# RH030_2.net
KiCad netlist of a schematic drawn in EAGLE
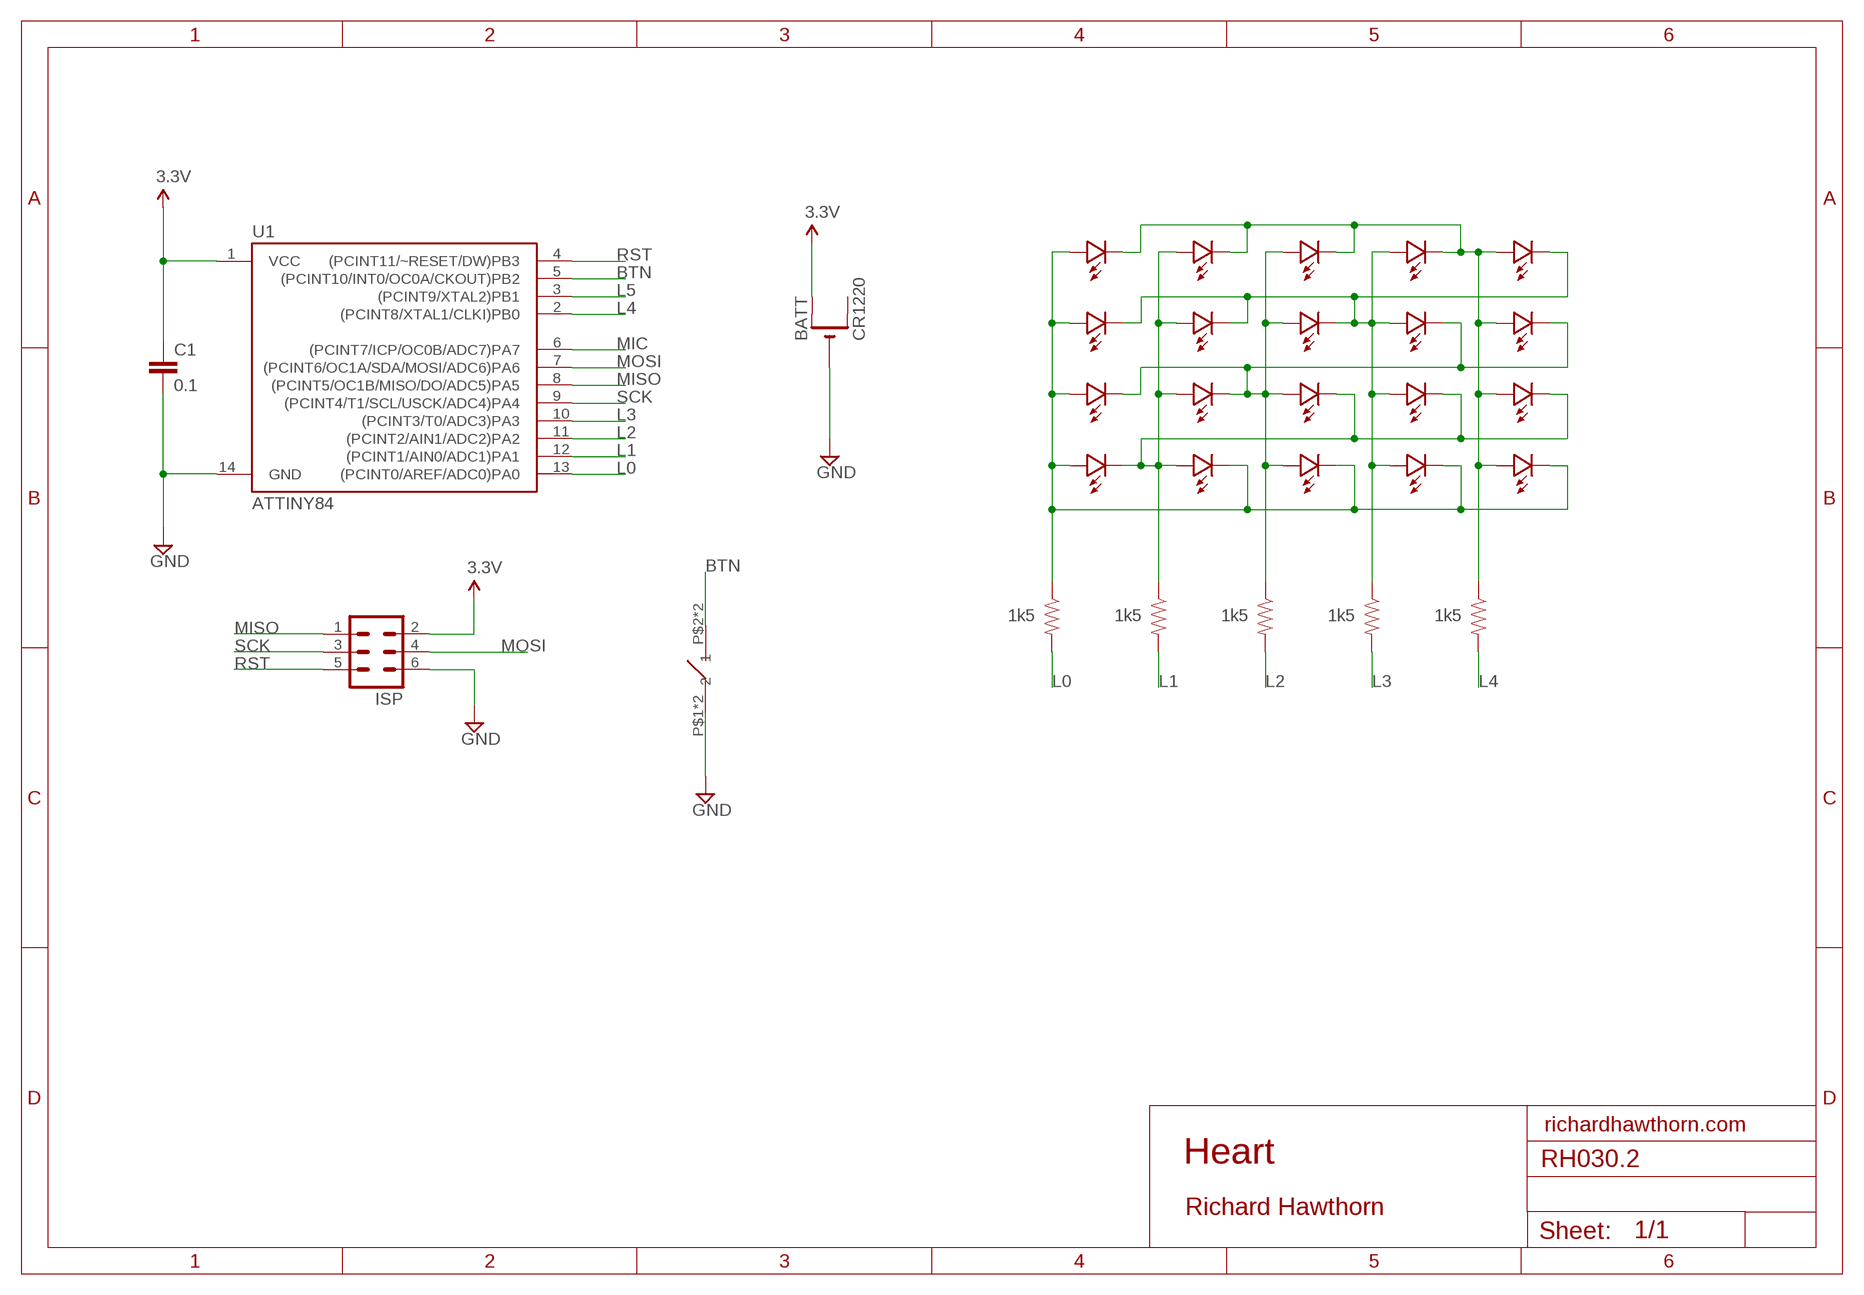
[diagram p0: schematic, sheet 1]

(export (version "E")
  (design (tool "Eeschema 10.0.6"))
  (components
    (comp (ref "BATT")
      (value "CR1220")
      (footprint "eagle-import:CR1220-SMD")
      (libsource (lib "eagle-import") (part "CR1220SMT"))
    )
    (comp (ref "BTN1")
      (value "TURTLE-3PIN")
      (footprint "eagle-import:TURTLE-3PIN")
      (libsource (lib "eagle-import") (part "TURTLE-3PIN"))
    )
    (comp (ref "C1")
      (value "0.1")
      (footprint "eagle-import:0603-CAP")
      (libsource (lib "eagle-import") (part "CAP0603-CAP"))
    )
    (comp (ref "ISP")
      (value "MA03-2")
      (footprint "eagle-import:MA03-2")
      (libsource (lib "eagle-import") (part "MA03-2"))
    )
    (comp (ref "LED1")
      (value "LED0603")
      (footprint "eagle-import:0603-LED")
      (libsource (lib "eagle-import") (part "LED0603"))
    )
    (comp (ref "LED2")
      (value "LED0603")
      (footprint "eagle-import:0603-LED")
      (libsource (lib "eagle-import") (part "LED0603"))
    )
    (comp (ref "LED3")
      (value "LED0603")
      (footprint "eagle-import:0603-LED")
      (libsource (lib "eagle-import") (part "LED0603"))
    )
    (comp (ref "LED4")
      (value "LED0603")
      (footprint "eagle-import:0603-LED")
      (libsource (lib "eagle-import") (part "LED0603"))
    )
    (comp (ref "LED5")
      (value "LED0603")
      (footprint "eagle-import:0603-LED")
      (libsource (lib "eagle-import") (part "LED0603"))
    )
    (comp (ref "LED6")
      (value "LED0603")
      (footprint "eagle-import:0603-LED")
      (libsource (lib "eagle-import") (part "LED0603"))
    )
    (comp (ref "LED7")
      (value "LED0603")
      (footprint "eagle-import:0603-LED")
      (libsource (lib "eagle-import") (part "LED0603"))
    )
    (comp (ref "LED8")
      (value "LED0603")
      (footprint "eagle-import:0603-LED")
      (libsource (lib "eagle-import") (part "LED0603"))
    )
    (comp (ref "LED9")
      (value "LED0603")
      (footprint "eagle-import:0603-LED")
      (libsource (lib "eagle-import") (part "LED0603"))
    )
    (comp (ref "LED10")
      (value "LED0603")
      (footprint "eagle-import:0603-LED")
      (libsource (lib "eagle-import") (part "LED0603"))
    )
    (comp (ref "LED11")
      (value "LED0603")
      (footprint "eagle-import:0603-LED")
      (libsource (lib "eagle-import") (part "LED0603"))
    )
    (comp (ref "LED12")
      (value "LED0603")
      (footprint "eagle-import:0603-LED")
      (libsource (lib "eagle-import") (part "LED0603"))
    )
    (comp (ref "LED13")
      (value "LED0603")
      (footprint "eagle-import:0603-LED")
      (libsource (lib "eagle-import") (part "LED0603"))
    )
    (comp (ref "LED14")
      (value "LED0603")
      (footprint "eagle-import:0603-LED")
      (libsource (lib "eagle-import") (part "LED0603"))
    )
    (comp (ref "LED15")
      (value "LED0603")
      (footprint "eagle-import:0603-LED")
      (libsource (lib "eagle-import") (part "LED0603"))
    )
    (comp (ref "LED16")
      (value "LED0603")
      (footprint "eagle-import:0603-LED")
      (libsource (lib "eagle-import") (part "LED0603"))
    )
    (comp (ref "LED17")
      (value "LED0603")
      (footprint "eagle-import:0603-LED")
      (libsource (lib "eagle-import") (part "LED0603"))
    )
    (comp (ref "LED18")
      (value "LED0603")
      (footprint "eagle-import:0603-LED")
      (libsource (lib "eagle-import") (part "LED0603"))
    )
    (comp (ref "LED19")
      (value "LED0603")
      (footprint "eagle-import:0603-LED")
      (libsource (lib "eagle-import") (part "LED0603"))
    )
    (comp (ref "LED20")
      (value "LED0603")
      (footprint "eagle-import:0603-LED")
      (libsource (lib "eagle-import") (part "LED0603"))
    )
    (comp (ref "R1")
      (value "1k5")
      (footprint "eagle-import:0603-RES")
      (libsource (lib "eagle-import") (part "RESISTOR0603-RES"))
    )
    (comp (ref "R2")
      (value "1k5")
      (footprint "eagle-import:0603-RES")
      (libsource (lib "eagle-import") (part "RESISTOR0603-RES"))
    )
    (comp (ref "R3")
      (value "1k5")
      (footprint "eagle-import:0603-RES")
      (libsource (lib "eagle-import") (part "RESISTOR0603-RES"))
    )
    (comp (ref "R4")
      (value "1k5")
      (footprint "eagle-import:0603-RES")
      (libsource (lib "eagle-import") (part "RESISTOR0603-RES"))
    )
    (comp (ref "R5")
      (value "1k5")
      (footprint "eagle-import:0603-RES")
      (libsource (lib "eagle-import") (part "RESISTOR0603-RES"))
    )
    (comp (ref "U1")
      (value "ATTINY84")
      (footprint "eagle-import:SO14")
      (libsource (lib "eagle-import") (part "ATTINY84"))
    )
  )
  (nets
    (net (code "1") (name "/BTN") (class "Default")
      (node (ref "BTN1") (pin "P$2") (pinfunction "2_P$2") (pintype "bidirectional"))
      (node (ref "BTN1") (pin "P$4") (pinfunction "2_P$4") (pintype "bidirectional"))
      (node (ref "U1") (pin "5") (pinfunction "(PCINT10/INT0/OC0A/CKOUT)PB2_5") (pintype "bidirectional"))
    )
    (net (code "2") (name "/L0") (class "Default")
      (node (ref "R1") (pin "2") (pinfunction "2_2") (pintype "passive"))
      (node (ref "U1") (pin "13") (pinfunction "(PCINT0/AREF/ADC0)PA0_13") (pintype "bidirectional"))
    )
    (net (code "3") (name "/L1") (class "Default")
      (node (ref "R2") (pin "2") (pinfunction "2_2") (pintype "passive"))
      (node (ref "U1") (pin "12") (pinfunction "(PCINT1/AIN0/ADC1)PA1_12") (pintype "bidirectional"))
    )
    (net (code "4") (name "/L2") (class "Default")
      (node (ref "R3") (pin "2") (pinfunction "2_2") (pintype "passive"))
      (node (ref "U1") (pin "11") (pinfunction "(PCINT2/AIN1/ADC2)PA2_11") (pintype "bidirectional"))
    )
    (net (code "5") (name "/L3") (class "Default")
      (node (ref "R4") (pin "2") (pinfunction "2_2") (pintype "passive"))
      (node (ref "U1") (pin "10") (pinfunction "(PCINT3/T0/ADC3)PA3_10") (pintype "bidirectional"))
    )
    (net (code "6") (name "/L4") (class "Default")
      (node (ref "R5") (pin "2") (pinfunction "2_2") (pintype "passive"))
      (node (ref "U1") (pin "2") (pinfunction "(PCINT8/XTAL1/CLKI)PB0_2") (pintype "bidirectional"))
    )
    (net (code "7") (name "/L5") (class "Default")
      (node (ref "U1") (pin "3") (pinfunction "(PCINT9/XTAL2)PB1_3") (pintype "bidirectional"))
    )
    (net (code "8") (name "/MIC") (class "Default")
      (node (ref "U1") (pin "6") (pinfunction "(PCINT7/ICP/OC0B/ADC7)PA7_6") (pintype "bidirectional"))
    )
    (net (code "9") (name "/MISO") (class "Default")
      (node (ref "ISP") (pin "1") (pinfunction "1_1") (pintype "passive"))
      (node (ref "U1") (pin "8") (pinfunction "(PCINT5/OC1B/MISO/DO/ADC5)PA5_8") (pintype "bidirectional"))
    )
    (net (code "10") (name "/MOSI") (class "Default")
      (node (ref "ISP") (pin "4") (pinfunction "4_4") (pintype "passive"))
      (node (ref "U1") (pin "7") (pinfunction "(PCINT6/OC1A/SDA/MOSI/ADC6)PA6_7") (pintype "bidirectional"))
    )
    (net (code "11") (name "/RST") (class "Default")
      (node (ref "ISP") (pin "5") (pinfunction "5_5") (pintype "passive"))
      (node (ref "U1") (pin "4") (pinfunction "(PCINT11/~{RESET/DW})PB3_4") (pintype "bidirectional"))
    )
    (net (code "12") (name "/SCK") (class "Default")
      (node (ref "ISP") (pin "3") (pinfunction "3_3") (pintype "passive"))
      (node (ref "U1") (pin "9") (pinfunction "(PCINT4/T1/SCL/USCK/ADC4)PA4_9") (pintype "bidirectional"))
    )
    (net (code "13") (name "3.3V") (class "Default")
      (node (ref "BATT") (pin "+$1") (pinfunction "+_+$1") (pintype "passive"))
      (node (ref "C1") (pin "1") (pinfunction "1_1") (pintype "passive"))
      (node (ref "ISP") (pin "2") (pinfunction "2_2") (pintype "passive"))
      (node (ref "U1") (pin "1") (pinfunction "VCC_1") (pintype "bidirectional"))
    )
    (net (code "14") (name "GND") (class "Default")
      (node (ref "BATT") (pin "-") (pinfunction "-_-") (pintype "passive"))
      (node (ref "BTN1") (pin "P$1") (pinfunction "1_P$1") (pintype "bidirectional"))
      (node (ref "BTN1") (pin "P$3") (pinfunction "1_P$3") (pintype "bidirectional"))
      (node (ref "C1") (pin "2") (pinfunction "2_2") (pintype "passive"))
      (node (ref "ISP") (pin "6") (pinfunction "6_6") (pintype "passive"))
      (node (ref "U1") (pin "14") (pinfunction "GND_14") (pintype "bidirectional"))
    )
    (net (code "15") (name "Net-(LED1-PadMINUS)") (class "Default")
      (node (ref "LED1") (pin "MINUS") (pinfunction "MINUS_MINUS") (pintype "passive"))
      (node (ref "LED10") (pin "PLUS") (pinfunction "PLUS_PLUS") (pintype "passive"))
      (node (ref "LED15") (pin "PLUS") (pinfunction "PLUS_PLUS") (pintype "passive"))
      (node (ref "LED2") (pin "MINUS") (pinfunction "MINUS_MINUS") (pintype "passive"))
      (node (ref "LED20") (pin "PLUS") (pinfunction "PLUS_PLUS") (pintype "passive"))
      (node (ref "LED3") (pin "MINUS") (pinfunction "MINUS_MINUS") (pintype "passive"))
      (node (ref "LED4") (pin "MINUS") (pinfunction "MINUS_MINUS") (pintype "passive"))
      (node (ref "LED5") (pin "PLUS") (pinfunction "PLUS_PLUS") (pintype "passive"))
      (node (ref "R5") (pin "1") (pinfunction "1_1") (pintype "passive"))
    )
    (net (code "16") (name "Net-(LED1-PadPLUS)") (class "Default")
      (node (ref "LED1") (pin "PLUS") (pinfunction "PLUS_PLUS") (pintype "passive"))
      (node (ref "LED11") (pin "PLUS") (pinfunction "PLUS_PLUS") (pintype "passive"))
      (node (ref "LED16") (pin "PLUS") (pinfunction "PLUS_PLUS") (pintype "passive"))
      (node (ref "LED17") (pin "MINUS") (pinfunction "MINUS_MINUS") (pintype "passive"))
      (node (ref "LED18") (pin "MINUS") (pinfunction "MINUS_MINUS") (pintype "passive"))
      (node (ref "LED19") (pin "MINUS") (pinfunction "MINUS_MINUS") (pintype "passive"))
      (node (ref "LED20") (pin "MINUS") (pinfunction "MINUS_MINUS") (pintype "passive"))
      (node (ref "LED6") (pin "PLUS") (pinfunction "PLUS_PLUS") (pintype "passive"))
      (node (ref "R1") (pin "1") (pinfunction "1_1") (pintype "passive"))
    )
    (net (code "17") (name "Net-(LED10-PadMINUS)") (class "Default")
      (node (ref "LED10") (pin "MINUS") (pinfunction "MINUS_MINUS") (pintype "passive"))
      (node (ref "LED11") (pin "MINUS") (pinfunction "MINUS_MINUS") (pintype "passive"))
      (node (ref "LED12") (pin "MINUS") (pinfunction "MINUS_MINUS") (pintype "passive"))
      (node (ref "LED13") (pin "PLUS") (pinfunction "PLUS_PLUS") (pintype "passive"))
      (node (ref "LED18") (pin "PLUS") (pinfunction "PLUS_PLUS") (pintype "passive"))
      (node (ref "LED3") (pin "PLUS") (pinfunction "PLUS_PLUS") (pintype "passive"))
      (node (ref "LED8") (pin "PLUS") (pinfunction "PLUS_PLUS") (pintype "passive"))
      (node (ref "LED9") (pin "MINUS") (pinfunction "MINUS_MINUS") (pintype "passive"))
      (node (ref "R3") (pin "1") (pinfunction "1_1") (pintype "passive"))
    )
    (net (code "18") (name "Net-(LED12-PadPLUS)") (class "Default")
      (node (ref "LED12") (pin "PLUS") (pinfunction "PLUS_PLUS") (pintype "passive"))
      (node (ref "LED13") (pin "MINUS") (pinfunction "MINUS_MINUS") (pintype "passive"))
      (node (ref "LED14") (pin "MINUS") (pinfunction "MINUS_MINUS") (pintype "passive"))
      (node (ref "LED15") (pin "MINUS") (pinfunction "MINUS_MINUS") (pintype "passive"))
      (node (ref "LED16") (pin "MINUS") (pinfunction "MINUS_MINUS") (pintype "passive"))
      (node (ref "LED17") (pin "PLUS") (pinfunction "PLUS_PLUS") (pintype "passive"))
      (node (ref "LED2") (pin "PLUS") (pinfunction "PLUS_PLUS") (pintype "passive"))
      (node (ref "LED7") (pin "PLUS") (pinfunction "PLUS_PLUS") (pintype "passive"))
      (node (ref "R2") (pin "1") (pinfunction "1_1") (pintype "passive"))
    )
    (net (code "19") (name "Net-(LED14-PadPLUS)") (class "Default")
      (node (ref "LED14") (pin "PLUS") (pinfunction "PLUS_PLUS") (pintype "passive"))
      (node (ref "LED19") (pin "PLUS") (pinfunction "PLUS_PLUS") (pintype "passive"))
      (node (ref "LED4") (pin "PLUS") (pinfunction "PLUS_PLUS") (pintype "passive"))
      (node (ref "LED5") (pin "MINUS") (pinfunction "MINUS_MINUS") (pintype "passive"))
      (node (ref "LED6") (pin "MINUS") (pinfunction "MINUS_MINUS") (pintype "passive"))
      (node (ref "LED7") (pin "MINUS") (pinfunction "MINUS_MINUS") (pintype "passive"))
      (node (ref "LED8") (pin "MINUS") (pinfunction "MINUS_MINUS") (pintype "passive"))
      (node (ref "LED9") (pin "PLUS") (pinfunction "PLUS_PLUS") (pintype "passive"))
      (node (ref "R4") (pin "1") (pinfunction "1_1") (pintype "passive"))
    )
    (net (code "20") (name "unconnected-(BATT-+1-Pad+$2)") (class "Default")
      (node (ref "BATT") (pin "+$2") (pinfunction "+1_+$2") (pintype "passive"))
    )
  )
)
